# passive_balancing.net
KiCad netlist of a schematic drawn in Altium Designer
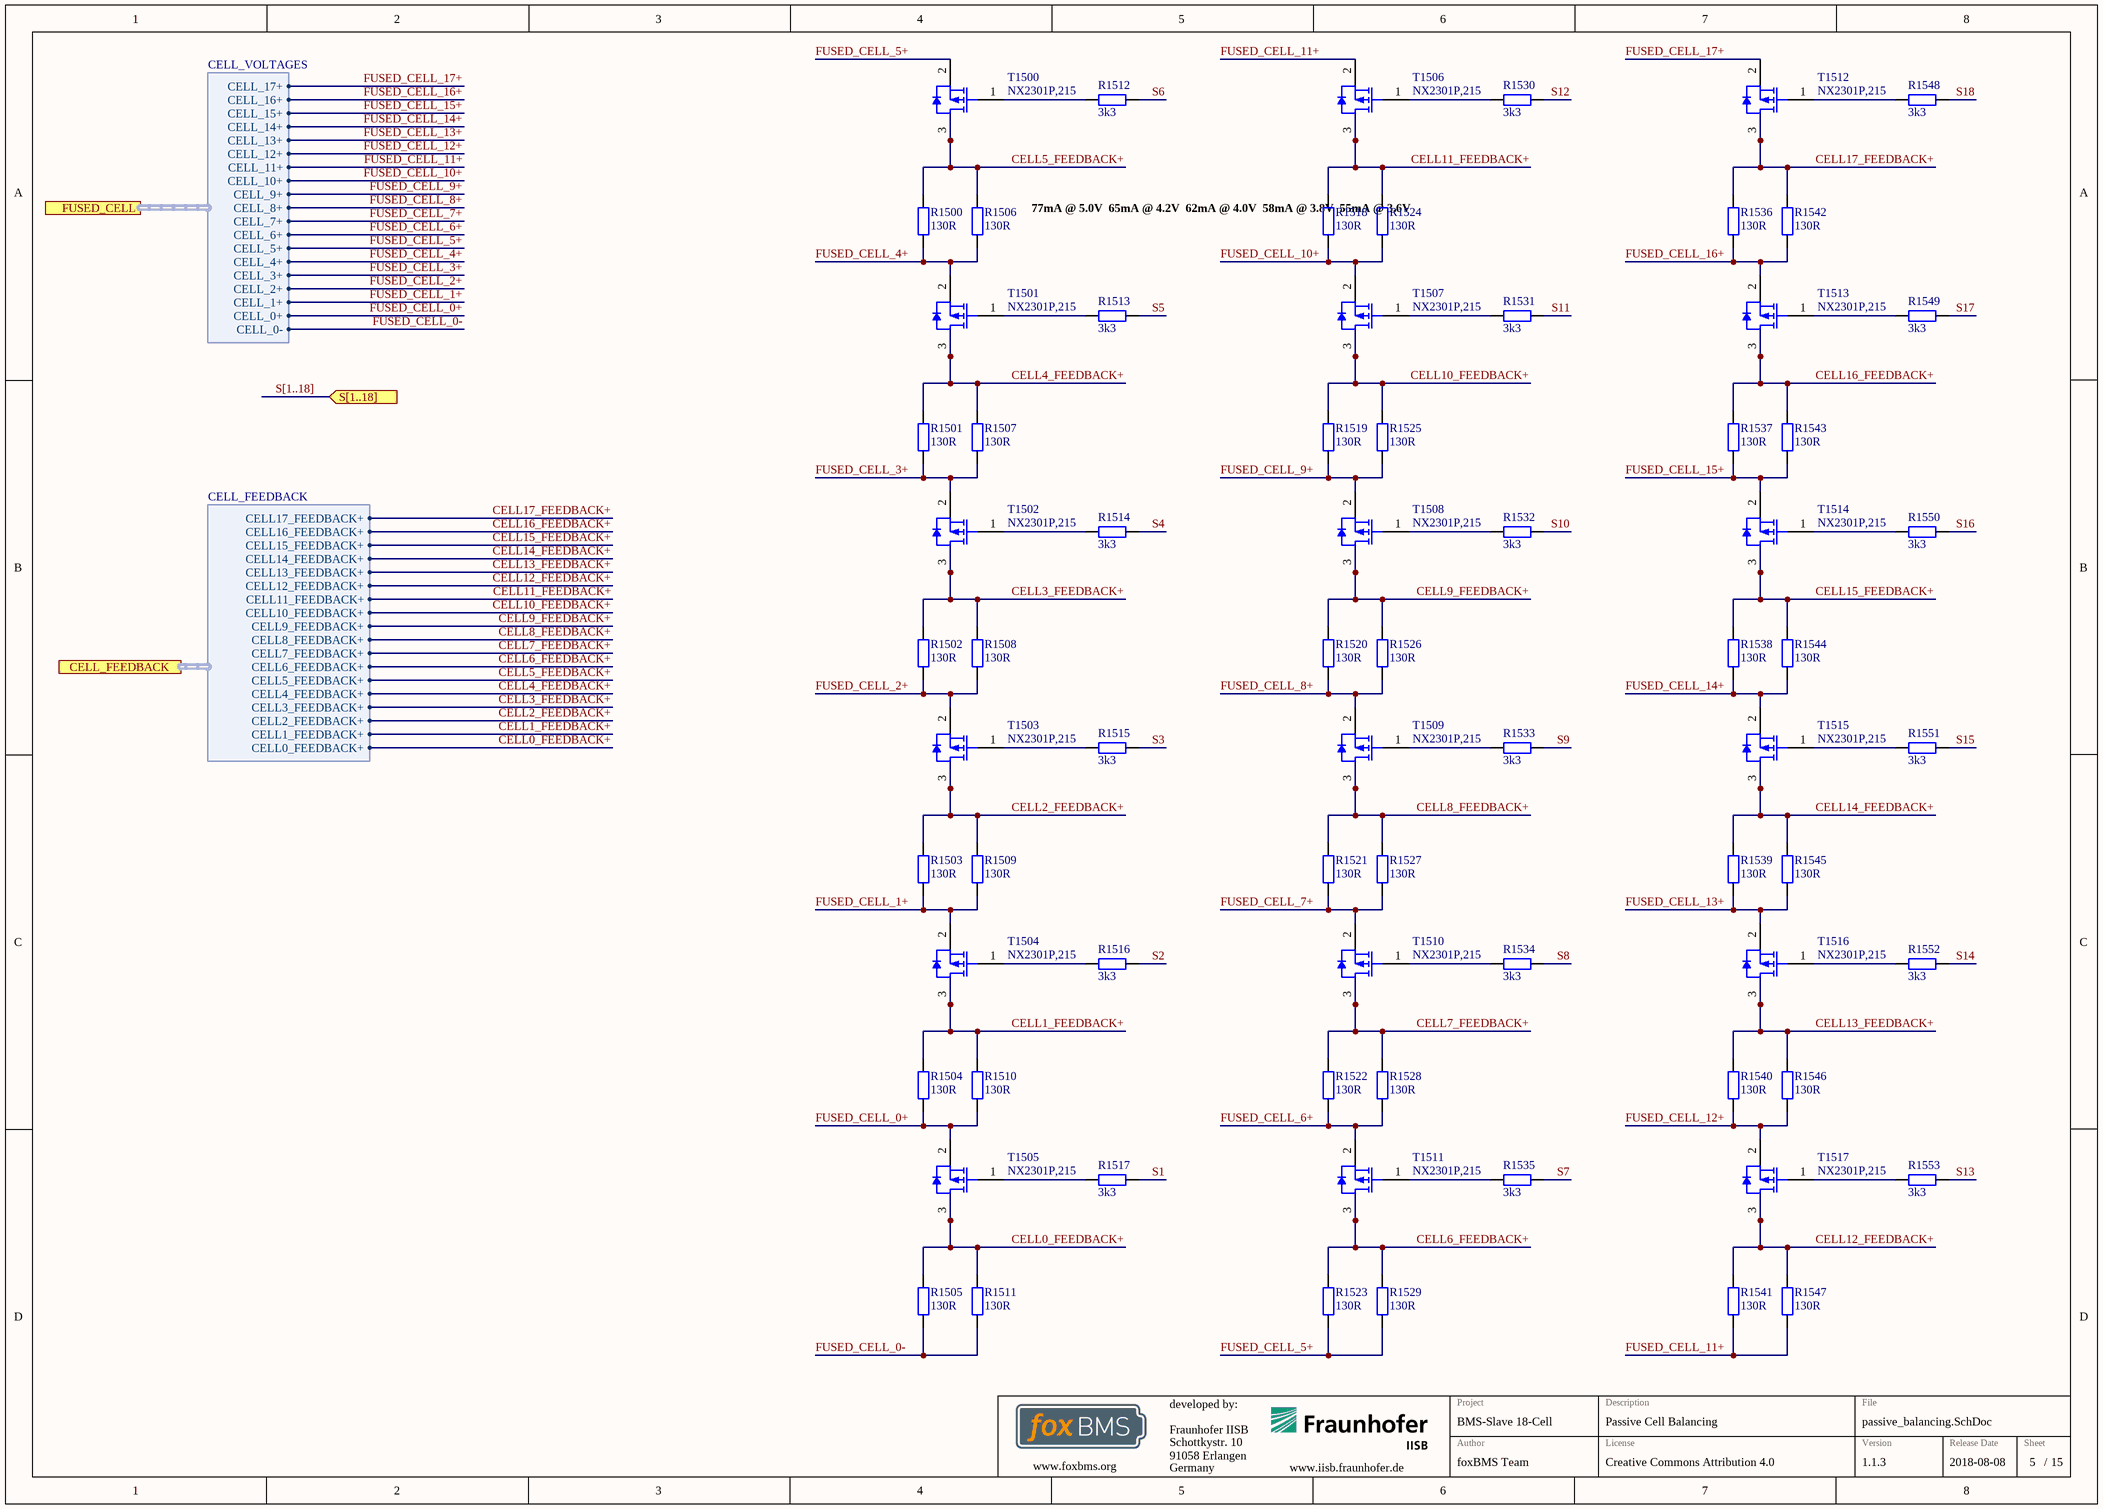
[diagram p0: passive_balancing.SchDoc]

(export (version "E")
  (design (tool "Eeschema 10.0.6"))
  (components
    (comp (ref "R1500")
      (value "130R")
      (footprint "RESC5025X07N")
      (description "SMD Resistor 130R 2010")
      (fields (field (name "PART NUMBER") "gen_R_130R_2010") (field (name "TOLERANCE") "5%"))
      (libsource (lib "OE750") (part "R"))
    )
    (comp (ref "R1501")
      (value "130R")
      (footprint "RESC5025X07N")
      (description "SMD Resistor 130R 2010")
      (fields (field (name "PART NUMBER") "gen_R_130R_2010") (field (name "TOLERANCE") "5%"))
      (libsource (lib "OE750") (part "R"))
    )
    (comp (ref "R1502")
      (value "130R")
      (footprint "RESC5025X07N")
      (description "SMD Resistor 130R 2010")
      (fields (field (name "PART NUMBER") "gen_R_130R_2010") (field (name "TOLERANCE") "5%"))
      (libsource (lib "OE750") (part "R"))
    )
    (comp (ref "R1503")
      (value "130R")
      (footprint "RESC5025X07N")
      (description "SMD Resistor 130R 2010")
      (fields (field (name "PART NUMBER") "gen_R_130R_2010") (field (name "TOLERANCE") "5%"))
      (libsource (lib "OE750") (part "R"))
    )
    (comp (ref "R1504")
      (value "130R")
      (footprint "RESC5025X07N")
      (description "SMD Resistor 130R 2010")
      (fields (field (name "PART NUMBER") "gen_R_130R_2010") (field (name "TOLERANCE") "5%"))
      (libsource (lib "OE750") (part "R"))
    )
    (comp (ref "R1505")
      (value "130R")
      (footprint "RESC5025X07N")
      (description "SMD Resistor 130R 2010")
      (fields (field (name "PART NUMBER") "gen_R_130R_2010") (field (name "TOLERANCE") "5%"))
      (libsource (lib "OE750") (part "R"))
    )
    (comp (ref "R1506")
      (value "130R")
      (footprint "RESC5025X07N")
      (description "SMD Resistor 130R 2010")
      (fields (field (name "PART NUMBER") "gen_R_130R_2010") (field (name "TOLERANCE") "5%"))
      (libsource (lib "OE750") (part "R"))
    )
    (comp (ref "R1507")
      (value "130R")
      (footprint "RESC5025X07N")
      (description "SMD Resistor 130R 2010")
      (fields (field (name "PART NUMBER") "gen_R_130R_2010") (field (name "TOLERANCE") "5%"))
      (libsource (lib "OE750") (part "R"))
    )
    (comp (ref "R1508")
      (value "130R")
      (footprint "RESC5025X07N")
      (description "SMD Resistor 130R 2010")
      (fields (field (name "PART NUMBER") "gen_R_130R_2010") (field (name "TOLERANCE") "5%"))
      (libsource (lib "OE750") (part "R"))
    )
    (comp (ref "R1509")
      (value "130R")
      (footprint "RESC5025X07N")
      (description "SMD Resistor 130R 2010")
      (fields (field (name "PART NUMBER") "gen_R_130R_2010") (field (name "TOLERANCE") "5%"))
      (libsource (lib "OE750") (part "R"))
    )
    (comp (ref "R1510")
      (value "130R")
      (footprint "RESC5025X07N")
      (description "SMD Resistor 130R 2010")
      (fields (field (name "PART NUMBER") "gen_R_130R_2010") (field (name "TOLERANCE") "5%"))
      (libsource (lib "OE750") (part "R"))
    )
    (comp (ref "R1511")
      (value "130R")
      (footprint "RESC5025X07N")
      (description "SMD Resistor 130R 2010")
      (fields (field (name "PART NUMBER") "gen_R_130R_2010") (field (name "TOLERANCE") "5%"))
      (libsource (lib "OE750") (part "R"))
    )
    (comp (ref "R1512")
      (value "3k3")
      (footprint "RESC1608X05N")
      (description "SMD Resistor 3k3 0603")
      (fields (field (name "PART NUMBER") "gen_R_3k3_0603") (field (name "TOLERANCE") "1%"))
      (libsource (lib "OE750") (part "R"))
    )
    (comp (ref "R1513")
      (value "3k3")
      (footprint "RESC1608X05N")
      (description "SMD Resistor 3k3 0603")
      (fields (field (name "PART NUMBER") "gen_R_3k3_0603") (field (name "TOLERANCE") "1%"))
      (libsource (lib "OE750") (part "R"))
    )
    (comp (ref "R1514")
      (value "3k3")
      (footprint "RESC1608X05N")
      (description "SMD Resistor 3k3 0603")
      (fields (field (name "PART NUMBER") "gen_R_3k3_0603") (field (name "TOLERANCE") "1%"))
      (libsource (lib "OE750") (part "R"))
    )
    (comp (ref "R1515")
      (value "3k3")
      (footprint "RESC1608X05N")
      (description "SMD Resistor 3k3 0603")
      (fields (field (name "PART NUMBER") "gen_R_3k3_0603") (field (name "TOLERANCE") "1%"))
      (libsource (lib "OE750") (part "R"))
    )
    (comp (ref "R1516")
      (value "3k3")
      (footprint "RESC1608X05N")
      (description "SMD Resistor 3k3 0603")
      (fields (field (name "PART NUMBER") "gen_R_3k3_0603") (field (name "TOLERANCE") "1%"))
      (libsource (lib "OE750") (part "R"))
    )
    (comp (ref "R1517")
      (value "3k3")
      (footprint "RESC1608X05N")
      (description "SMD Resistor 3k3 0603")
      (fields (field (name "PART NUMBER") "gen_R_3k3_0603") (field (name "TOLERANCE") "1%"))
      (libsource (lib "OE750") (part "R"))
    )
    (comp (ref "R1518")
      (value "130R")
      (footprint "RESC5025X07N")
      (description "SMD Resistor 130R 2010")
      (fields (field (name "PART NUMBER") "gen_R_130R_2010") (field (name "TOLERANCE") "5%"))
      (libsource (lib "OE750") (part "R"))
    )
    (comp (ref "R1519")
      (value "130R")
      (footprint "RESC5025X07N")
      (description "SMD Resistor 130R 2010")
      (fields (field (name "PART NUMBER") "gen_R_130R_2010") (field (name "TOLERANCE") "5%"))
      (libsource (lib "OE750") (part "R"))
    )
    (comp (ref "R1520")
      (value "130R")
      (footprint "RESC5025X07N")
      (description "SMD Resistor 130R 2010")
      (fields (field (name "PART NUMBER") "gen_R_130R_2010") (field (name "TOLERANCE") "5%"))
      (libsource (lib "OE750") (part "R"))
    )
    (comp (ref "R1521")
      (value "130R")
      (footprint "RESC5025X07N")
      (description "SMD Resistor 130R 2010")
      (fields (field (name "PART NUMBER") "gen_R_130R_2010") (field (name "TOLERANCE") "5%"))
      (libsource (lib "OE750") (part "R"))
    )
    (comp (ref "R1522")
      (value "130R")
      (footprint "RESC5025X07N")
      (description "SMD Resistor 130R 2010")
      (fields (field (name "PART NUMBER") "gen_R_130R_2010") (field (name "TOLERANCE") "5%"))
      (libsource (lib "OE750") (part "R"))
    )
    (comp (ref "R1523")
      (value "130R")
      (footprint "RESC5025X07N")
      (description "SMD Resistor 130R 2010")
      (fields (field (name "PART NUMBER") "gen_R_130R_2010") (field (name "TOLERANCE") "5%"))
      (libsource (lib "OE750") (part "R"))
    )
    (comp (ref "R1524")
      (value "130R")
      (footprint "RESC5025X07N")
      (description "SMD Resistor 130R 2010")
      (fields (field (name "PART NUMBER") "gen_R_130R_2010") (field (name "TOLERANCE") "5%"))
      (libsource (lib "OE750") (part "R"))
    )
    (comp (ref "R1525")
      (value "130R")
      (footprint "RESC5025X07N")
      (description "SMD Resistor 130R 2010")
      (fields (field (name "PART NUMBER") "gen_R_130R_2010") (field (name "TOLERANCE") "5%"))
      (libsource (lib "OE750") (part "R"))
    )
    (comp (ref "R1526")
      (value "130R")
      (footprint "RESC5025X07N")
      (description "SMD Resistor 130R 2010")
      (fields (field (name "PART NUMBER") "gen_R_130R_2010") (field (name "TOLERANCE") "5%"))
      (libsource (lib "OE750") (part "R"))
    )
    (comp (ref "R1527")
      (value "130R")
      (footprint "RESC5025X07N")
      (description "SMD Resistor 130R 2010")
      (fields (field (name "PART NUMBER") "gen_R_130R_2010") (field (name "TOLERANCE") "5%"))
      (libsource (lib "OE750") (part "R"))
    )
    (comp (ref "R1528")
      (value "130R")
      (footprint "RESC5025X07N")
      (description "SMD Resistor 130R 2010")
      (fields (field (name "PART NUMBER") "gen_R_130R_2010") (field (name "TOLERANCE") "5%"))
      (libsource (lib "OE750") (part "R"))
    )
    (comp (ref "R1529")
      (value "130R")
      (footprint "RESC5025X07N")
      (description "SMD Resistor 130R 2010")
      (fields (field (name "PART NUMBER") "gen_R_130R_2010") (field (name "TOLERANCE") "5%"))
      (libsource (lib "OE750") (part "R"))
    )
    (comp (ref "R1530")
      (value "3k3")
      (footprint "RESC1608X05N")
      (description "SMD Resistor 3k3 0603")
      (fields (field (name "PART NUMBER") "gen_R_3k3_0603") (field (name "TOLERANCE") "1%"))
      (libsource (lib "OE750") (part "R"))
    )
    (comp (ref "R1531")
      (value "3k3")
      (footprint "RESC1608X05N")
      (description "SMD Resistor 3k3 0603")
      (fields (field (name "PART NUMBER") "gen_R_3k3_0603") (field (name "TOLERANCE") "1%"))
      (libsource (lib "OE750") (part "R"))
    )
    (comp (ref "R1532")
      (value "3k3")
      (footprint "RESC1608X05N")
      (description "SMD Resistor 3k3 0603")
      (fields (field (name "PART NUMBER") "gen_R_3k3_0603") (field (name "TOLERANCE") "1%"))
      (libsource (lib "OE750") (part "R"))
    )
    (comp (ref "R1533")
      (value "3k3")
      (footprint "RESC1608X05N")
      (description "SMD Resistor 3k3 0603")
      (fields (field (name "PART NUMBER") "gen_R_3k3_0603") (field (name "TOLERANCE") "1%"))
      (libsource (lib "OE750") (part "R"))
    )
    (comp (ref "R1534")
      (value "3k3")
      (footprint "RESC1608X05N")
      (description "SMD Resistor 3k3 0603")
      (fields (field (name "PART NUMBER") "gen_R_3k3_0603") (field (name "TOLERANCE") "1%"))
      (libsource (lib "OE750") (part "R"))
    )
    (comp (ref "R1535")
      (value "3k3")
      (footprint "RESC1608X05N")
      (description "SMD Resistor 3k3 0603")
      (fields (field (name "PART NUMBER") "gen_R_3k3_0603") (field (name "TOLERANCE") "1%"))
      (libsource (lib "OE750") (part "R"))
    )
    (comp (ref "R1536")
      (value "130R")
      (footprint "RESC5025X07N")
      (description "SMD Resistor 130R 2010")
      (fields (field (name "PART NUMBER") "gen_R_130R_2010") (field (name "TOLERANCE") "5%"))
      (libsource (lib "OE750") (part "R"))
    )
    (comp (ref "R1537")
      (value "130R")
      (footprint "RESC5025X07N")
      (description "SMD Resistor 130R 2010")
      (fields (field (name "PART NUMBER") "gen_R_130R_2010") (field (name "TOLERANCE") "5%"))
      (libsource (lib "OE750") (part "R"))
    )
    (comp (ref "R1538")
      (value "130R")
      (footprint "RESC5025X07N")
      (description "SMD Resistor 130R 2010")
      (fields (field (name "PART NUMBER") "gen_R_130R_2010") (field (name "TOLERANCE") "5%"))
      (libsource (lib "OE750") (part "R"))
    )
    (comp (ref "R1539")
      (value "130R")
      (footprint "RESC5025X07N")
      (description "SMD Resistor 130R 2010")
      (fields (field (name "PART NUMBER") "gen_R_130R_2010") (field (name "TOLERANCE") "5%"))
      (libsource (lib "OE750") (part "R"))
    )
    (comp (ref "R1540")
      (value "130R")
      (footprint "RESC5025X07N")
      (description "SMD Resistor 130R 2010")
      (fields (field (name "PART NUMBER") "gen_R_130R_2010") (field (name "TOLERANCE") "5%"))
      (libsource (lib "OE750") (part "R"))
    )
    (comp (ref "R1541")
      (value "130R")
      (footprint "RESC5025X07N")
      (description "SMD Resistor 130R 2010")
      (fields (field (name "PART NUMBER") "gen_R_130R_2010") (field (name "TOLERANCE") "5%"))
      (libsource (lib "OE750") (part "R"))
    )
    (comp (ref "R1542")
      (value "130R")
      (footprint "RESC5025X07N")
      (description "SMD Resistor 130R 2010")
      (fields (field (name "PART NUMBER") "gen_R_130R_2010") (field (name "TOLERANCE") "5%"))
      (libsource (lib "OE750") (part "R"))
    )
    (comp (ref "R1543")
      (value "130R")
      (footprint "RESC5025X07N")
      (description "SMD Resistor 130R 2010")
      (fields (field (name "PART NUMBER") "gen_R_130R_2010") (field (name "TOLERANCE") "5%"))
      (libsource (lib "OE750") (part "R"))
    )
    (comp (ref "R1544")
      (value "130R")
      (footprint "RESC5025X07N")
      (description "SMD Resistor 130R 2010")
      (fields (field (name "PART NUMBER") "gen_R_130R_2010") (field (name "TOLERANCE") "5%"))
      (libsource (lib "OE750") (part "R"))
    )
    (comp (ref "R1545")
      (value "130R")
      (footprint "RESC5025X07N")
      (description "SMD Resistor 130R 2010")
      (fields (field (name "PART NUMBER") "gen_R_130R_2010") (field (name "TOLERANCE") "5%"))
      (libsource (lib "OE750") (part "R"))
    )
    (comp (ref "R1546")
      (value "130R")
      (footprint "RESC5025X07N")
      (description "SMD Resistor 130R 2010")
      (fields (field (name "PART NUMBER") "gen_R_130R_2010") (field (name "TOLERANCE") "5%"))
      (libsource (lib "OE750") (part "R"))
    )
    (comp (ref "R1547")
      (value "130R")
      (footprint "RESC5025X07N")
      (description "SMD Resistor 130R 2010")
      (fields (field (name "PART NUMBER") "gen_R_130R_2010") (field (name "TOLERANCE") "5%"))
      (libsource (lib "OE750") (part "R"))
    )
    (comp (ref "R1548")
      (value "3k3")
      (footprint "RESC1608X05N")
      (description "SMD Resistor 3k3 0603")
      (fields (field (name "PART NUMBER") "gen_R_3k3_0603") (field (name "TOLERANCE") "1%"))
      (libsource (lib "OE750") (part "R"))
    )
    (comp (ref "R1549")
      (value "3k3")
      (footprint "RESC1608X05N")
      (description "SMD Resistor 3k3 0603")
      (fields (field (name "PART NUMBER") "gen_R_3k3_0603") (field (name "TOLERANCE") "1%"))
      (libsource (lib "OE750") (part "R"))
    )
    (comp (ref "R1550")
      (value "3k3")
      (footprint "RESC1608X05N")
      (description "SMD Resistor 3k3 0603")
      (fields (field (name "PART NUMBER") "gen_R_3k3_0603") (field (name "TOLERANCE") "1%"))
      (libsource (lib "OE750") (part "R"))
    )
    (comp (ref "R1551")
      (value "3k3")
      (footprint "RESC1608X05N")
      (description "SMD Resistor 3k3 0603")
      (fields (field (name "PART NUMBER") "gen_R_3k3_0603") (field (name "TOLERANCE") "1%"))
      (libsource (lib "OE750") (part "R"))
    )
    (comp (ref "R1552")
      (value "3k3")
      (footprint "RESC1608X05N")
      (description "SMD Resistor 3k3 0603")
      (fields (field (name "PART NUMBER") "gen_R_3k3_0603") (field (name "TOLERANCE") "1%"))
      (libsource (lib "OE750") (part "R"))
    )
    (comp (ref "R1553")
      (value "3k3")
      (footprint "RESC1608X05N")
      (description "SMD Resistor 3k3 0603")
      (fields (field (name "PART NUMBER") "gen_R_3k3_0603") (field (name "TOLERANCE") "1%"))
      (libsource (lib "OE750") (part "R"))
    )
    (comp (ref "T1500")
      (value "NX2301P,215")
      (footprint "NXP-SOT23_N")
      (description "P-Channel Trench MOSFET, -20 V, -2 A, -55 to 150 degC, 3-Pin SOT23, Tape and Reel")
      (fields (field (name "MANUFACTURER") "NXP Semiconductors"))
      (libsource (lib "Altium Content Vault") (part "NXP-PMOS-GSD-3"))
    )
    (comp (ref "T1501")
      (value "NX2301P,215")
      (footprint "NXP-SOT23_N")
      (description "P-Channel Trench MOSFET, -20 V, -2 A, -55 to 150 degC, 3-Pin SOT23, Tape and Reel")
      (fields (field (name "MANUFACTURER") "NXP Semiconductors"))
      (libsource (lib "Altium Content Vault") (part "NXP-PMOS-GSD-3"))
    )
    (comp (ref "T1502")
      (value "NX2301P,215")
      (footprint "NXP-SOT23_N")
      (description "P-Channel Trench MOSFET, -20 V, -2 A, -55 to 150 degC, 3-Pin SOT23, Tape and Reel")
      (fields (field (name "MANUFACTURER") "NXP Semiconductors"))
      (libsource (lib "Altium Content Vault") (part "NXP-PMOS-GSD-3"))
    )
    (comp (ref "T1503")
      (value "NX2301P,215")
      (footprint "NXP-SOT23_N")
      (description "P-Channel Trench MOSFET, -20 V, -2 A, -55 to 150 degC, 3-Pin SOT23, Tape and Reel")
      (fields (field (name "MANUFACTURER") "NXP Semiconductors"))
      (libsource (lib "Altium Content Vault") (part "NXP-PMOS-GSD-3"))
    )
    (comp (ref "T1504")
      (value "NX2301P,215")
      (footprint "NXP-SOT23_N")
      (description "P-Channel Trench MOSFET, -20 V, -2 A, -55 to 150 degC, 3-Pin SOT23, Tape and Reel")
      (fields (field (name "MANUFACTURER") "NXP Semiconductors"))
      (libsource (lib "Altium Content Vault") (part "NXP-PMOS-GSD-3"))
    )
    (comp (ref "T1505")
      (value "NX2301P,215")
      (footprint "NXP-SOT23_N")
      (description "P-Channel Trench MOSFET, -20 V, -2 A, -55 to 150 degC, 3-Pin SOT23, Tape and Reel")
      (fields (field (name "MANUFACTURER") "NXP Semiconductors"))
      (libsource (lib "Altium Content Vault") (part "NXP-PMOS-GSD-3"))
    )
    (comp (ref "T1506")
      (value "NX2301P,215")
      (footprint "NXP-SOT23_N")
      (description "P-Channel Trench MOSFET, -20 V, -2 A, -55 to 150 degC, 3-Pin SOT23, Tape and Reel")
      (fields (field (name "MANUFACTURER") "NXP Semiconductors"))
      (libsource (lib "Altium Content Vault") (part "NXP-PMOS-GSD-3"))
    )
    (comp (ref "T1507")
      (value "NX2301P,215")
      (footprint "NXP-SOT23_N")
      (description "P-Channel Trench MOSFET, -20 V, -2 A, -55 to 150 degC, 3-Pin SOT23, Tape and Reel")
      (fields (field (name "MANUFACTURER") "NXP Semiconductors"))
      (libsource (lib "Altium Content Vault") (part "NXP-PMOS-GSD-3"))
    )
    (comp (ref "T1508")
      (value "NX2301P,215")
      (footprint "NXP-SOT23_N")
      (description "P-Channel Trench MOSFET, -20 V, -2 A, -55 to 150 degC, 3-Pin SOT23, Tape and Reel")
      (fields (field (name "MANUFACTURER") "NXP Semiconductors"))
      (libsource (lib "Altium Content Vault") (part "NXP-PMOS-GSD-3"))
    )
    (comp (ref "T1509")
      (value "NX2301P,215")
      (footprint "NXP-SOT23_N")
      (description "P-Channel Trench MOSFET, -20 V, -2 A, -55 to 150 degC, 3-Pin SOT23, Tape and Reel")
      (fields (field (name "MANUFACTURER") "NXP Semiconductors"))
      (libsource (lib "Altium Content Vault") (part "NXP-PMOS-GSD-3"))
    )
    (comp (ref "T1510")
      (value "NX2301P,215")
      (footprint "NXP-SOT23_N")
      (description "P-Channel Trench MOSFET, -20 V, -2 A, -55 to 150 degC, 3-Pin SOT23, Tape and Reel")
      (fields (field (name "MANUFACTURER") "NXP Semiconductors"))
      (libsource (lib "Altium Content Vault") (part "NXP-PMOS-GSD-3"))
    )
    (comp (ref "T1511")
      (value "NX2301P,215")
      (footprint "NXP-SOT23_N")
      (description "P-Channel Trench MOSFET, -20 V, -2 A, -55 to 150 degC, 3-Pin SOT23, Tape and Reel")
      (fields (field (name "MANUFACTURER") "NXP Semiconductors"))
      (libsource (lib "Altium Content Vault") (part "NXP-PMOS-GSD-3"))
    )
    (comp (ref "T1512")
      (value "NX2301P,215")
      (footprint "NXP-SOT23_N")
      (description "P-Channel Trench MOSFET, -20 V, -2 A, -55 to 150 degC, 3-Pin SOT23, Tape and Reel")
      (fields (field (name "MANUFACTURER") "NXP Semiconductors"))
      (libsource (lib "Altium Content Vault") (part "NXP-PMOS-GSD-3"))
    )
    (comp (ref "T1513")
      (value "NX2301P,215")
      (footprint "NXP-SOT23_N")
      (description "P-Channel Trench MOSFET, -20 V, -2 A, -55 to 150 degC, 3-Pin SOT23, Tape and Reel")
      (fields (field (name "MANUFACTURER") "NXP Semiconductors"))
      (libsource (lib "Altium Content Vault") (part "NXP-PMOS-GSD-3"))
    )
    (comp (ref "T1514")
      (value "NX2301P,215")
      (footprint "NXP-SOT23_N")
      (description "P-Channel Trench MOSFET, -20 V, -2 A, -55 to 150 degC, 3-Pin SOT23, Tape and Reel")
      (fields (field (name "MANUFACTURER") "NXP Semiconductors"))
      (libsource (lib "Altium Content Vault") (part "NXP-PMOS-GSD-3"))
    )
    (comp (ref "T1515")
      (value "NX2301P,215")
      (footprint "NXP-SOT23_N")
      (description "P-Channel Trench MOSFET, -20 V, -2 A, -55 to 150 degC, 3-Pin SOT23, Tape and Reel")
      (fields (field (name "MANUFACTURER") "NXP Semiconductors"))
      (libsource (lib "Altium Content Vault") (part "NXP-PMOS-GSD-3"))
    )
    (comp (ref "T1516")
      (value "NX2301P,215")
      (footprint "NXP-SOT23_N")
      (description "P-Channel Trench MOSFET, -20 V, -2 A, -55 to 150 degC, 3-Pin SOT23, Tape and Reel")
      (fields (field (name "MANUFACTURER") "NXP Semiconductors"))
      (libsource (lib "Altium Content Vault") (part "NXP-PMOS-GSD-3"))
    )
    (comp (ref "T1517")
      (value "NX2301P,215")
      (footprint "NXP-SOT23_N")
      (description "P-Channel Trench MOSFET, -20 V, -2 A, -55 to 150 degC, 3-Pin SOT23, Tape and Reel")
      (fields (field (name "MANUFACTURER") "NXP Semiconductors"))
      (libsource (lib "Altium Content Vault") (part "NXP-PMOS-GSD-3"))
    )
  )
  (nets
    (net (code "3") (name "/CELL0_FEEDBACK+") (class "Default")
      (node (ref "R1505") (pin "2") (pinfunction "2_2") (pintype "passive"))
      (node (ref "R1511") (pin "2") (pinfunction "2_2") (pintype "passive"))
      (node (ref "T1505") (pin "3") (pinfunction "D_3") (pintype "passive"))
    )
    (net (code "4") (name "/CELL1_FEEDBACK+") (class "Default")
      (node (ref "R1504") (pin "2") (pinfunction "2_2") (pintype "passive"))
      (node (ref "R1510") (pin "2") (pinfunction "2_2") (pintype "passive"))
      (node (ref "T1504") (pin "3") (pinfunction "D_3") (pintype "passive"))
    )
    (net (code "5") (name "/CELL2_FEEDBACK+") (class "Default")
      (node (ref "R1503") (pin "2") (pinfunction "2_2") (pintype "passive"))
      (node (ref "R1509") (pin "2") (pinfunction "2_2") (pintype "passive"))
      (node (ref "T1503") (pin "3") (pinfunction "D_3") (pintype "passive"))
    )
    (net (code "6") (name "/CELL3_FEEDBACK+") (class "Default")
      (node (ref "R1502") (pin "2") (pinfunction "2_2") (pintype "passive"))
      (node (ref "R1508") (pin "2") (pinfunction "2_2") (pintype "passive"))
      (node (ref "T1502") (pin "3") (pinfunction "D_3") (pintype "passive"))
    )
    (net (code "7") (name "/CELL4_FEEDBACK+") (class "Default")
      (node (ref "R1501") (pin "2") (pinfunction "2_2") (pintype "passive"))
      (node (ref "R1507") (pin "2") (pinfunction "2_2") (pintype "passive"))
      (node (ref "T1501") (pin "3") (pinfunction "D_3") (pintype "passive"))
    )
    (net (code "8") (name "/CELL5_FEEDBACK+") (class "Default")
      (node (ref "R1500") (pin "2") (pinfunction "2_2") (pintype "passive"))
      (node (ref "R1506") (pin "2") (pinfunction "2_2") (pintype "passive"))
      (node (ref "T1500") (pin "3") (pinfunction "D_3") (pintype "passive"))
    )
    (net (code "9") (name "/CELL6_FEEDBACK+") (class "Default")
      (node (ref "R1523") (pin "2") (pinfunction "2_2") (pintype "passive"))
      (node (ref "R1529") (pin "2") (pinfunction "2_2") (pintype "passive"))
      (node (ref "T1511") (pin "3") (pinfunction "D_3") (pintype "passive"))
    )
    (net (code "10") (name "/CELL7_FEEDBACK+") (class "Default")
      (node (ref "R1522") (pin "2") (pinfunction "2_2") (pintype "passive"))
      (node (ref "R1528") (pin "2") (pinfunction "2_2") (pintype "passive"))
      (node (ref "T1510") (pin "3") (pinfunction "D_3") (pintype "passive"))
    )
    (net (code "11") (name "/CELL8_FEEDBACK+") (class "Default")
      (node (ref "R1521") (pin "2") (pinfunction "2_2") (pintype "passive"))
      (node (ref "R1527") (pin "2") (pinfunction "2_2") (pintype "passive"))
      (node (ref "T1509") (pin "3") (pinfunction "D_3") (pintype "passive"))
    )
    (net (code "12") (name "/CELL9_FEEDBACK+") (class "Default")
      (node (ref "R1520") (pin "2") (pinfunction "2_2") (pintype "passive"))
      (node (ref "R1526") (pin "2") (pinfunction "2_2") (pintype "passive"))
      (node (ref "T1508") (pin "3") (pinfunction "D_3") (pintype "passive"))
    )
    (net (code "13") (name "/CELL10_FEEDBACK+") (class "Default")
      (node (ref "R1519") (pin "2") (pinfunction "2_2") (pintype "passive"))
      (node (ref "R1525") (pin "2") (pinfunction "2_2") (pintype "passive"))
      (node (ref "T1507") (pin "3") (pinfunction "D_3") (pintype "passive"))
    )
    (net (code "14") (name "/CELL11_FEEDBACK+") (class "Default")
      (node (ref "R1518") (pin "2") (pinfunction "2_2") (pintype "passive"))
      (node (ref "R1524") (pin "2") (pinfunction "2_2") (pintype "passive"))
      (node (ref "T1506") (pin "3") (pinfunction "D_3") (pintype "passive"))
    )
    (net (code "15") (name "/CELL12_FEEDBACK+") (class "Default")
      (node (ref "R1541") (pin "2") (pinfunction "2_2") (pintype "passive"))
      (node (ref "R1547") (pin "2") (pinfunction "2_2") (pintype "passive"))
      (node (ref "T1517") (pin "3") (pinfunction "D_3") (pintype "passive"))
    )
    (net (code "16") (name "/CELL13_FEEDBACK+") (class "Default")
      (node (ref "R1540") (pin "2") (pinfunction "2_2") (pintype "passive"))
      (node (ref "R1546") (pin "2") (pinfunction "2_2") (pintype "passive"))
      (node (ref "T1516") (pin "3") (pinfunction "D_3") (pintype "passive"))
    )
    (net (code "17") (name "/CELL14_FEEDBACK+") (class "Default")
      (node (ref "R1539") (pin "2") (pinfunction "2_2") (pintype "passive"))
      (node (ref "R1545") (pin "2") (pinfunction "2_2") (pintype "passive"))
      (node (ref "T1515") (pin "3") (pinfunction "D_3") (pintype "passive"))
    )
    (net (code "18") (name "/CELL15_FEEDBACK+") (class "Default")
      (node (ref "R1538") (pin "2") (pinfunction "2_2") (pintype "passive"))
      (node (ref "R1544") (pin "2") (pinfunction "2_2") (pintype "passive"))
      (node (ref "T1514") (pin "3") (pinfunction "D_3") (pintype "passive"))
    )
    (net (code "19") (name "/CELL16_FEEDBACK+") (class "Default")
      (node (ref "R1537") (pin "2") (pinfunction "2_2") (pintype "passive"))
      (node (ref "R1543") (pin "2") (pinfunction "2_2") (pintype "passive"))
      (node (ref "T1513") (pin "3") (pinfunction "D_3") (pintype "passive"))
    )
    (net (code "20") (name "/CELL17_FEEDBACK+") (class "Default")
      (node (ref "R1536") (pin "2") (pinfunction "2_2") (pintype "passive"))
      (node (ref "R1542") (pin "2") (pinfunction "2_2") (pintype "passive"))
      (node (ref "T1512") (pin "3") (pinfunction "D_3") (pintype "passive"))
    )
    (net (code "21") (name "/FUSED_CELL_0+") (class "Default")
      (node (ref "R1504") (pin "1") (pinfunction "1_1") (pintype "passive"))
      (node (ref "R1510") (pin "1") (pinfunction "1_1") (pintype "passive"))
      (node (ref "T1505") (pin "2") (pinfunction "S_2") (pintype "passive"))
    )
    (net (code "22") (name "/FUSED_CELL_0-") (class "Default")
      (node (ref "R1505") (pin "1") (pinfunction "1_1") (pintype "passive"))
      (node (ref "R1511") (pin "1") (pinfunction "1_1") (pintype "passive"))
    )
    (net (code "23") (name "/FUSED_CELL_1+") (class "Default")
      (node (ref "R1503") (pin "1") (pinfunction "1_1") (pintype "passive"))
      (node (ref "R1509") (pin "1") (pinfunction "1_1") (pintype "passive"))
      (node (ref "T1504") (pin "2") (pinfunction "S_2") (pintype "passive"))
    )
    (net (code "24") (name "/FUSED_CELL_2+") (class "Default")
      (node (ref "R1502") (pin "1") (pinfunction "1_1") (pintype "passive"))
      (node (ref "R1508") (pin "1") (pinfunction "1_1") (pintype "passive"))
      (node (ref "T1503") (pin "2") (pinfunction "S_2") (pintype "passive"))
    )
    (net (code "25") (name "/FUSED_CELL_3+") (class "Default")
      (node (ref "R1501") (pin "1") (pinfunction "1_1") (pintype "passive"))
      (node (ref "R1507") (pin "1") (pinfunction "1_1") (pintype "passive"))
      (node (ref "T1502") (pin "2") (pinfunction "S_2") (pintype "passive"))
    )
    (net (code "26") (name "/FUSED_CELL_4+") (class "Default")
      (node (ref "R1500") (pin "1") (pinfunction "1_1") (pintype "passive"))
      (node (ref "R1506") (pin "1") (pinfunction "1_1") (pintype "passive"))
      (node (ref "T1501") (pin "2") (pinfunction "S_2") (pintype "passive"))
    )
    (net (code "27") (name "/FUSED_CELL_5+") (class "Default")
      (node (ref "R1523") (pin "1") (pinfunction "1_1") (pintype "passive"))
      (node (ref "R1529") (pin "1") (pinfunction "1_1") (pintype "passive"))
      (node (ref "T1500") (pin "2") (pinfunction "S_2") (pintype "passive"))
    )
    (net (code "28") (name "/FUSED_CELL_6+") (class "Default")
      (node (ref "R1522") (pin "1") (pinfunction "1_1") (pintype "passive"))
      (node (ref "R1528") (pin "1") (pinfunction "1_1") (pintype "passive"))
      (node (ref "T1511") (pin "2") (pinfunction "S_2") (pintype "passive"))
    )
    (net (code "29") (name "/FUSED_CELL_7+") (class "Default")
      (node (ref "R1521") (pin "1") (pinfunction "1_1") (pintype "passive"))
      (node (ref "R1527") (pin "1") (pinfunction "1_1") (pintype "passive"))
      (node (ref "T1510") (pin "2") (pinfunction "S_2") (pintype "passive"))
    )
    (net (code "30") (name "/FUSED_CELL_8+") (class "Default")
      (node (ref "R1520") (pin "1") (pinfunction "1_1") (pintype "passive"))
      (node (ref "R1526") (pin "1") (pinfunction "1_1") (pintype "passive"))
      (node (ref "T1509") (pin "2") (pinfunction "S_2") (pintype "passive"))
    )
    (net (code "31") (name "/FUSED_CELL_9+") (class "Default")
      (node (ref "R1519") (pin "1") (pinfunction "1_1") (pintype "passive"))
      (node (ref "R1525") (pin "1") (pinfunction "1_1") (pintype "passive"))
      (node (ref "T1508") (pin "2") (pinfunction "S_2") (pintype "passive"))
    )
    (net (code "32") (name "/FUSED_CELL_10+") (class "Default")
      (node (ref "R1518") (pin "1") (pinfunction "1_1") (pintype "passive"))
      (node (ref "R1524") (pin "1") (pinfunction "1_1") (pintype "passive"))
      (node (ref "T1507") (pin "2") (pinfunction "S_2") (pintype "passive"))
    )
    (net (code "33") (name "/FUSED_CELL_11+") (class "Default")
      (node (ref "R1541") (pin "1") (pinfunction "1_1") (pintype "passive"))
      (node (ref "R1547") (pin "1") (pinfunction "1_1") (pintype "passive"))
      (node (ref "T1506") (pin "2") (pinfunction "S_2") (pintype "passive"))
    )
    (net (code "34") (name "/FUSED_CELL_12+") (class "Default")
      (node (ref "R1540") (pin "1") (pinfunction "1_1") (pintype "passive"))
      (node (ref "R1546") (pin "1") (pinfunction "1_1") (pintype "passive"))
      (node (ref "T1517") (pin "2") (pinfunction "S_2") (pintype "passive"))
    )
    (net (code "35") (name "/FUSED_CELL_13+") (class "Default")
      (node (ref "R1539") (pin "1") (pinfunction "1_1") (pintype "passive"))
      (node (ref "R1545") (pin "1") (pinfunction "1_1") (pintype "passive"))
      (node (ref "T1516") (pin "2") (pinfunction "S_2") (pintype "passive"))
    )
    (net (code "36") (name "/FUSED_CELL_14+") (class "Default")
      (node (ref "R1538") (pin "1") (pinfunction "1_1") (pintype "passive"))
      (node (ref "R1544") (pin "1") (pinfunction "1_1") (pintype "passive"))
      (node (ref "T1515") (pin "2") (pinfunction "S_2") (pintype "passive"))
    )
    (net (code "37") (name "/FUSED_CELL_15+") (class "Default")
      (node (ref "R1537") (pin "1") (pinfunction "1_1") (pintype "passive"))
      (node (ref "R1543") (pin "1") (pinfunction "1_1") (pintype "passive"))
      (node (ref "T1514") (pin "2") (pinfunction "S_2") (pintype "passive"))
    )
    (net (code "38") (name "/FUSED_CELL_16+") (class "Default")
      (node (ref "R1536") (pin "1") (pinfunction "1_1") (pintype "passive"))
      (node (ref "R1542") (pin "1") (pinfunction "1_1") (pintype "passive"))
      (node (ref "T1513") (pin "2") (pinfunction "S_2") (pintype "passive"))
    )
    (net (code "39") (name "/FUSED_CELL_17+") (class "Default")
      (node (ref "T1512") (pin "2") (pinfunction "S_2") (pintype "passive"))
    )
    (net (code "40") (name "/S1") (class "Default")
      (node (ref "R1517") (pin "2") (pinfunction "2_2") (pintype "passive"))
    )
    (net (code "41") (name "/S2") (class "Default")
      (node (ref "R1516") (pin "2") (pinfunction "2_2") (pintype "passive"))
    )
    (net (code "42") (name "/S3") (class "Default")
      (node (ref "R1515") (pin "2") (pinfunction "2_2") (pintype "passive"))
    )
    (net (code "43") (name "/S4") (class "Default")
      (node (ref "R1514") (pin "2") (pinfunction "2_2") (pintype "passive"))
    )
    (net (code "44") (name "/S5") (class "Default")
      (node (ref "R1513") (pin "2") (pinfunction "2_2") (pintype "passive"))
    )
    (net (code "45") (name "/S6") (class "Default")
      (node (ref "R1512") (pin "2") (pinfunction "2_2") (pintype "passive"))
    )
    (net (code "46") (name "/S7") (class "Default")
      (node (ref "R1535") (pin "2") (pinfunction "2_2") (pintype "passive"))
    )
    (net (code "47") (name "/S8") (class "Default")
      (node (ref "R1534") (pin "2") (pinfunction "2_2") (pintype "passive"))
    )
    (net (code "48") (name "/S9") (class "Default")
      (node (ref "R1533") (pin "2") (pinfunction "2_2") (pintype "passive"))
    )
    (net (code "49") (name "/S10") (class "Default")
      (node (ref "R1532") (pin "2") (pinfunction "2_2") (pintype "passive"))
    )
    (net (code "50") (name "/S11") (class "Default")
      (node (ref "R1531") (pin "2") (pinfunction "2_2") (pintype "passive"))
    )
    (net (code "51") (name "/S12") (class "Default")
      (node (ref "R1530") (pin "2") (pinfunction "2_2") (pintype "passive"))
    )
    (net (code "52") (name "/S13") (class "Default")
      (node (ref "R1553") (pin "2") (pinfunction "2_2") (pintype "passive"))
    )
    (net (code "53") (name "/S14") (class "Default")
      (node (ref "R1552") (pin "2") (pinfunction "2_2") (pintype "passive"))
    )
    (net (code "54") (name "/S15") (class "Default")
      (node (ref "R1551") (pin "2") (pinfunction "2_2") (pintype "passive"))
    )
    (net (code "55") (name "/S16") (class "Default")
      (node (ref "R1550") (pin "2") (pinfunction "2_2") (pintype "passive"))
    )
    (net (code "56") (name "/S17") (class "Default")
      (node (ref "R1549") (pin "2") (pinfunction "2_2") (pintype "passive"))
    )
    (net (code "57") (name "/S18") (class "Default")
      (node (ref "R1548") (pin "2") (pinfunction "2_2") (pintype "passive"))
    )
    (net (code "61") (name "Net-(T1500-G)") (class "Default")
      (node (ref "R1512") (pin "1") (pinfunction "1_1") (pintype "passive"))
      (node (ref "T1500") (pin "1") (pinfunction "G_1") (pintype "passive"))
    )
    (net (code "62") (name "Net-(T1501-G)") (class "Default")
      (node (ref "R1513") (pin "1") (pinfunction "1_1") (pintype "passive"))
      (node (ref "T1501") (pin "1") (pinfunction "G_1") (pintype "passive"))
    )
    (net (code "63") (name "Net-(T1502-G)") (class "Default")
      (node (ref "R1514") (pin "1") (pinfunction "1_1") (pintype "passive"))
      (node (ref "T1502") (pin "1") (pinfunction "G_1") (pintype "passive"))
    )
    (net (code "64") (name "Net-(T1503-G)") (class "Default")
      (node (ref "R1515") (pin "1") (pinfunction "1_1") (pintype "passive"))
      (node (ref "T1503") (pin "1") (pinfunction "G_1") (pintype "passive"))
    )
    (net (code "65") (name "Net-(T1504-G)") (class "Default")
      (node (ref "R1516") (pin "1") (pinfunction "1_1") (pintype "passive"))
      (node (ref "T1504") (pin "1") (pinfunction "G_1") (pintype "passive"))
    )
    (net (code "66") (name "Net-(T1505-G)") (class "Default")
      (node (ref "R1517") (pin "1") (pinfunction "1_1") (pintype "passive"))
      (node (ref "T1505") (pin "1") (pinfunction "G_1") (pintype "passive"))
    )
    (net (code "67") (name "Net-(T1506-G)") (class "Default")
      (node (ref "R1530") (pin "1") (pinfunction "1_1") (pintype "passive"))
      (node (ref "T1506") (pin "1") (pinfunction "G_1") (pintype "passive"))
    )
    (net (code "68") (name "Net-(T1507-G)") (class "Default")
      (node (ref "R1531") (pin "1") (pinfunction "1_1") (pintype "passive"))
      (node (ref "T1507") (pin "1") (pinfunction "G_1") (pintype "passive"))
    )
    (net (code "69") (name "Net-(T1508-G)") (class "Default")
      (node (ref "R1532") (pin "1") (pinfunction "1_1") (pintype "passive"))
      (node (ref "T1508") (pin "1") (pinfunction "G_1") (pintype "passive"))
    )
    (net (code "70") (name "Net-(T1509-G)") (class "Default")
      (node (ref "R1533") (pin "1") (pinfunction "1_1") (pintype "passive"))
      (node (ref "T1509") (pin "1") (pinfunction "G_1") (pintype "passive"))
    )
    (net (code "71") (name "Net-(T1510-G)") (class "Default")
      (node (ref "R1534") (pin "1") (pinfunction "1_1") (pintype "passive"))
      (node (ref "T1510") (pin "1") (pinfunction "G_1") (pintype "passive"))
    )
    (net (code "72") (name "Net-(T1511-G)") (class "Default")
      (node (ref "R1535") (pin "1") (pinfunction "1_1") (pintype "passive"))
      (node (ref "T1511") (pin "1") (pinfunction "G_1") (pintype "passive"))
    )
    (net (code "73") (name "Net-(T1512-G)") (class "Default")
      (node (ref "R1548") (pin "1") (pinfunction "1_1") (pintype "passive"))
      (node (ref "T1512") (pin "1") (pinfunction "G_1") (pintype "passive"))
    )
    (net (code "74") (name "Net-(T1513-G)") (class "Default")
      (node (ref "R1549") (pin "1") (pinfunction "1_1") (pintype "passive"))
      (node (ref "T1513") (pin "1") (pinfunction "G_1") (pintype "passive"))
    )
    (net (code "75") (name "Net-(T1514-G)") (class "Default")
      (node (ref "R1550") (pin "1") (pinfunction "1_1") (pintype "passive"))
      (node (ref "T1514") (pin "1") (pinfunction "G_1") (pintype "passive"))
    )
    (net (code "76") (name "Net-(T1515-G)") (class "Default")
      (node (ref "R1551") (pin "1") (pinfunction "1_1") (pintype "passive"))
      (node (ref "T1515") (pin "1") (pinfunction "G_1") (pintype "passive"))
    )
    (net (code "77") (name "Net-(T1516-G)") (class "Default")
      (node (ref "R1552") (pin "1") (pinfunction "1_1") (pintype "passive"))
      (node (ref "T1516") (pin "1") (pinfunction "G_1") (pintype "passive"))
    )
    (net (code "78") (name "Net-(T1517-G)") (class "Default")
      (node (ref "R1553") (pin "1") (pinfunction "1_1") (pintype "passive"))
      (node (ref "T1517") (pin "1") (pinfunction "G_1") (pintype "passive"))
    )
  )
)
